# MotorAlarm2B.net
KiCad netlist of a schematic drawn in EAGLE
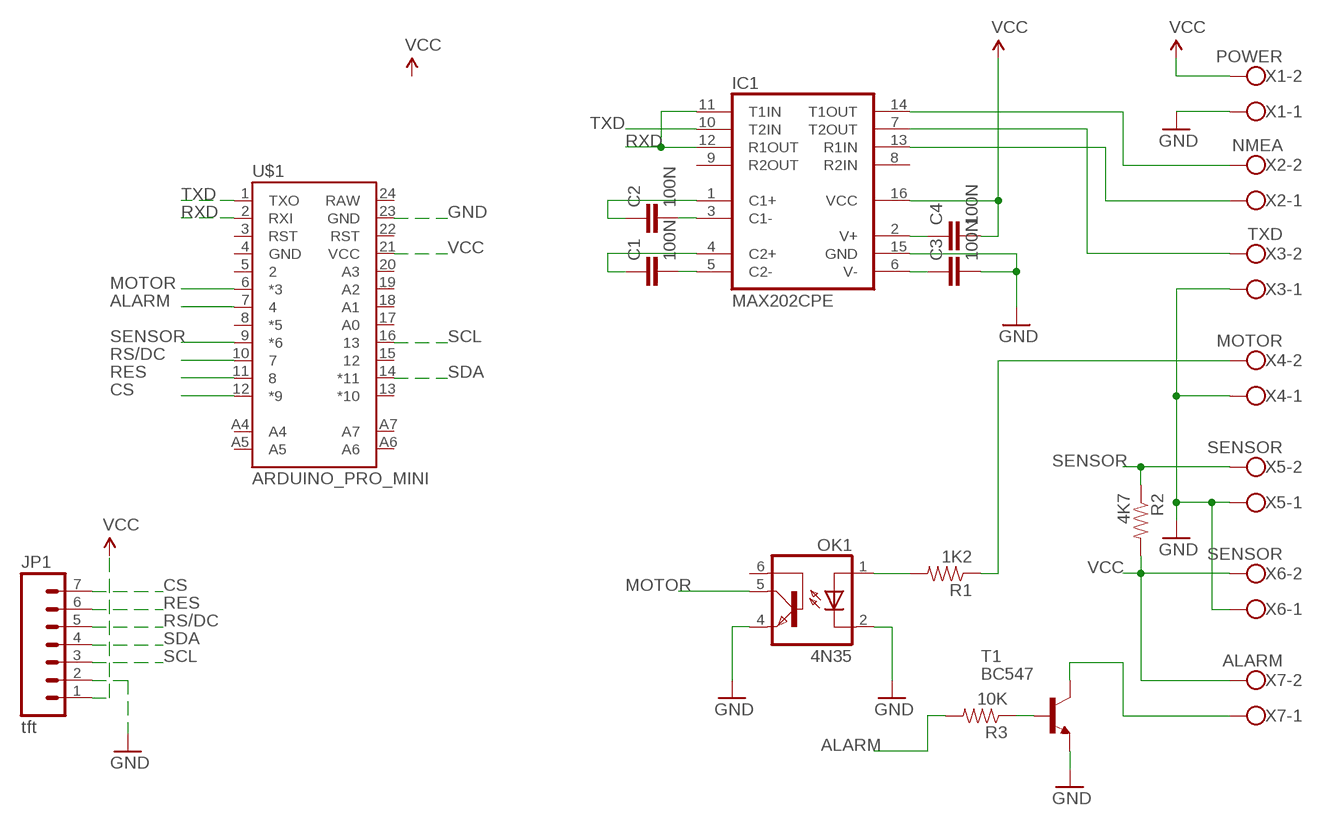
[diagram p0: schematic, sheet 1]

(export (version "E")
  (design (tool "Eeschema 10.0.6"))
  (components
    (comp (ref "C1")
      (value "100N")
      (footprint "eagle-import:CAP-PTH-SMALL")
      (libsource (lib "eagle-import") (part "CAPPTH"))
    )
    (comp (ref "C2")
      (value "100N")
      (footprint "eagle-import:CAP-PTH-SMALL")
      (libsource (lib "eagle-import") (part "CAPPTH"))
    )
    (comp (ref "C3")
      (value "100N")
      (footprint "eagle-import:CAP-PTH-SMALL")
      (libsource (lib "eagle-import") (part "CAPPTH"))
    )
    (comp (ref "C4")
      (value "100N")
      (footprint "eagle-import:CAP-PTH-SMALL")
      (libsource (lib "eagle-import") (part "CAPPTH"))
    )
    (comp (ref "IC1")
      (value "MAX202CPE")
      (footprint "eagle-import:DIL16")
      (fields (field (name "MF") "MAXIM") (field (name "MPN") "MAX202CPE+"))
      (libsource (lib "eagle-import") (part "MAX202CPE"))
    )
    (comp (ref "JP1")
      (value "tft")
      (footprint "eagle-import:1X07")
      (libsource (lib "eagle-import") (part "M07"))
    )
    (comp (ref "OK1")
      (value "4N35")
      (footprint "eagle-import:DIL06")
      (fields (field (name "MF") "FAIRCHILD SEMICONDUCTOR"))
      (libsource (lib "eagle-import") (part "4N35"))
    )
    (comp (ref "R1")
      (value "1K2")
      (footprint "eagle-import:AXIAL-0.4")
      (libsource (lib "eagle-import") (part "RESISTORPTH-1/4W"))
    )
    (comp (ref "R2")
      (value "4K7")
      (footprint "eagle-import:AXIAL-0.4")
      (libsource (lib "eagle-import") (part "RESISTORPTH-1/4W"))
    )
    (comp (ref "R3")
      (value "10K")
      (footprint "eagle-import:AXIAL-0.4")
      (libsource (lib "eagle-import") (part "RESISTORPTH-1/4W"))
    )
    (comp (ref "T1")
      (value "BC547")
      (footprint "eagle-import:TO92")
      (libsource (lib "eagle-import") (part "BC547"))
    )
    (comp (ref "U$1")
      (value "ARDUINO_PRO_MINI")
      (footprint "eagle-import:ARDUINO_PRO_MINI")
      (libsource (lib "eagle-import") (part "ARDUINO_PRO_MINI"))
    )
    (comp (ref "X1")
      (value "POWER")
      (footprint "eagle-import:W237-102")
      (fields (field (name "MPN") "237-102"))
      (libsource (lib "eagle-import") (part "W237-102"))
    )
    (comp (ref "X2")
      (value "NMEA")
      (footprint "eagle-import:W237-102")
      (fields (field (name "MPN") "237-102"))
      (libsource (lib "eagle-import") (part "W237-102"))
    )
    (comp (ref "X3")
      (value "TXD")
      (footprint "eagle-import:W237-102")
      (fields (field (name "MPN") "237-102"))
      (libsource (lib "eagle-import") (part "W237-102"))
    )
    (comp (ref "X4")
      (value "MOTOR")
      (footprint "eagle-import:W237-102")
      (fields (field (name "MPN") "237-102"))
      (libsource (lib "eagle-import") (part "W237-102"))
    )
    (comp (ref "X5")
      (value "SENSOR")
      (footprint "eagle-import:W237-102")
      (fields (field (name "MPN") "237-102"))
      (libsource (lib "eagle-import") (part "W237-102"))
    )
    (comp (ref "X6")
      (value "SENSOR")
      (footprint "eagle-import:W237-102")
      (fields (field (name "MPN") "237-102"))
      (libsource (lib "eagle-import") (part "W237-102"))
    )
    (comp (ref "X7")
      (value "ALARM")
      (footprint "eagle-import:W237-102")
      (fields (field (name "MPN") "237-102"))
      (libsource (lib "eagle-import") (part "W237-102"))
    )
  )
  (nets
    (net (code "1") (name "/ALARM") (class "Default")
      (node (ref "R3") (pin "P$2") (pinfunction "2_P$2") (pintype "passive"))
      (node (ref "U$1") (pin "7") (pinfunction "4_7") (pintype "bidirectional"))
    )
    (net (code "2") (name "/CS") (class "Default")
      (node (ref "JP1") (pin "7") (pinfunction "7_7") (pintype "passive"))
      (node (ref "U$1") (pin "12") (pinfunction "*9_12") (pintype "bidirectional"))
    )
    (net (code "3") (name "/MOTOR") (class "Default")
      (node (ref "OK1") (pin "5") (pinfunction "COL_5") (pintype "passive"))
      (node (ref "U$1") (pin "6") (pinfunction "*3_6") (pintype "bidirectional"))
    )
    (net (code "4") (name "/RES") (class "Default")
      (node (ref "JP1") (pin "6") (pinfunction "6_6") (pintype "passive"))
      (node (ref "U$1") (pin "11") (pinfunction "8_11") (pintype "bidirectional"))
    )
    (net (code "5") (name "/RS{slash}DC") (class "Default")
      (node (ref "JP1") (pin "5") (pinfunction "5_5") (pintype "passive"))
      (node (ref "U$1") (pin "10") (pinfunction "7_10") (pintype "bidirectional"))
    )
    (net (code "6") (name "/RXD") (class "Default")
      (node (ref "IC1") (pin "11") (pinfunction "T1IN_11") (pintype "input"))
      (node (ref "IC1") (pin "12") (pinfunction "R1OUT_12") (pintype "output"))
      (node (ref "U$1") (pin "2") (pinfunction "RXI_2") (pintype "bidirectional"))
    )
    (net (code "7") (name "/SCL") (class "Default")
      (node (ref "JP1") (pin "3") (pinfunction "3_3") (pintype "passive"))
      (node (ref "U$1") (pin "16") (pinfunction "13_16") (pintype "bidirectional"))
    )
    (net (code "8") (name "/SDA") (class "Default")
      (node (ref "JP1") (pin "4") (pinfunction "4_4") (pintype "passive"))
      (node (ref "U$1") (pin "14") (pinfunction "*11_14") (pintype "bidirectional"))
    )
    (net (code "9") (name "/SENSOR") (class "Default")
      (node (ref "R2") (pin "P$1") (pinfunction "1_P$1") (pintype "passive"))
      (node (ref "U$1") (pin "9") (pinfunction "*6_9") (pintype "bidirectional"))
      (node (ref "X5") (pin "2") (pinfunction "KL_2") (pintype "passive"))
    )
    (net (code "10") (name "/TXD") (class "Default")
      (node (ref "IC1") (pin "10") (pinfunction "T2IN_10") (pintype "input"))
      (node (ref "U$1") (pin "1") (pinfunction "TXO_1") (pintype "bidirectional"))
    )
    (net (code "11") (name "GND") (class "Default")
      (node (ref "C3") (pin "2") (pinfunction "2_2") (pintype "passive"))
      (node (ref "IC1") (pin "15") (pinfunction "GND_15") (pintype "power_in"))
      (node (ref "JP1") (pin "2") (pinfunction "2_2") (pintype "passive"))
      (node (ref "OK1") (pin "2") (pinfunction "C_2") (pintype "passive"))
      (node (ref "OK1") (pin "4") (pinfunction "EMI_4") (pintype "passive"))
      (node (ref "T1") (pin "1") (pinfunction "E_1") (pintype "passive"))
      (node (ref "U$1") (pin "23") (pinfunction "GND_23") (pintype "bidirectional"))
      (node (ref "X1") (pin "1") (pinfunction "KL_1") (pintype "passive"))
      (node (ref "X3") (pin "1") (pinfunction "KL_1") (pintype "passive"))
      (node (ref "X4") (pin "1") (pinfunction "KL_1") (pintype "passive"))
      (node (ref "X5") (pin "1") (pinfunction "KL_1") (pintype "passive"))
      (node (ref "X6") (pin "1") (pinfunction "KL_1") (pintype "passive"))
    )
    (net (code "12") (name "Net-(IC1-C1+)") (class "Default")
      (node (ref "C2") (pin "1") (pinfunction "1_1") (pintype "passive"))
      (node (ref "IC1") (pin "1") (pinfunction "C1+_1") (pintype "passive"))
    )
    (net (code "13") (name "Net-(IC1-C1-)") (class "Default")
      (node (ref "C2") (pin "2") (pinfunction "2_2") (pintype "passive"))
      (node (ref "IC1") (pin "3") (pinfunction "C1-_3") (pintype "passive"))
    )
    (net (code "14") (name "Net-(IC1-C2+)") (class "Default")
      (node (ref "C1") (pin "1") (pinfunction "1_1") (pintype "passive"))
      (node (ref "IC1") (pin "4") (pinfunction "C2+_4") (pintype "passive"))
    )
    (net (code "15") (name "Net-(IC1-C2-)") (class "Default")
      (node (ref "C1") (pin "2") (pinfunction "2_2") (pintype "passive"))
      (node (ref "IC1") (pin "5") (pinfunction "C2-_5") (pintype "passive"))
    )
    (net (code "16") (name "Net-(IC1-R1IN)") (class "Default")
      (node (ref "IC1") (pin "13") (pinfunction "R1IN_13") (pintype "input"))
      (node (ref "X2") (pin "1") (pinfunction "KL_1") (pintype "passive"))
    )
    (net (code "17") (name "Net-(IC1-T1OUT)") (class "Default")
      (node (ref "IC1") (pin "14") (pinfunction "T1OUT_14") (pintype "output"))
      (node (ref "X2") (pin "2") (pinfunction "KL_2") (pintype "passive"))
    )
    (net (code "18") (name "Net-(IC1-T2OUT)") (class "Default")
      (node (ref "IC1") (pin "7") (pinfunction "T2OUT_7") (pintype "output"))
      (node (ref "X3") (pin "2") (pinfunction "KL_2") (pintype "passive"))
    )
    (net (code "19") (name "Net-(IC1-V+)") (class "Default")
      (node (ref "C4") (pin "1") (pinfunction "1_1") (pintype "passive"))
      (node (ref "IC1") (pin "2") (pinfunction "V+_2") (pintype "power_in"))
    )
    (net (code "20") (name "Net-(IC1-V-)") (class "Default")
      (node (ref "C3") (pin "1") (pinfunction "1_1") (pintype "passive"))
      (node (ref "IC1") (pin "6") (pinfunction "V-_6") (pintype "power_in"))
    )
    (net (code "21") (name "Net-(OK1-A)") (class "Default")
      (node (ref "OK1") (pin "1") (pinfunction "A_1") (pintype "passive"))
      (node (ref "R1") (pin "P$2") (pinfunction "2_P$2") (pintype "passive"))
    )
    (net (code "22") (name "Net-(R1-1)") (class "Default")
      (node (ref "R1") (pin "P$1") (pinfunction "1_P$1") (pintype "passive"))
      (node (ref "X4") (pin "2") (pinfunction "KL_2") (pintype "passive"))
    )
    (net (code "23") (name "Net-(R3-1)") (class "Default")
      (node (ref "R3") (pin "P$1") (pinfunction "1_P$1") (pintype "passive"))
      (node (ref "T1") (pin "2") (pinfunction "B_2") (pintype "passive"))
    )
    (net (code "24") (name "Net-(T1-C)") (class "Default")
      (node (ref "T1") (pin "3") (pinfunction "C_3") (pintype "passive"))
      (node (ref "X7") (pin "1") (pinfunction "KL_1") (pintype "passive"))
    )
    (net (code "25") (name "VCC") (class "Default")
      (node (ref "C4") (pin "2") (pinfunction "2_2") (pintype "passive"))
      (node (ref "IC1") (pin "16") (pinfunction "VCC_16") (pintype "power_in"))
      (node (ref "JP1") (pin "1") (pinfunction "1_1") (pintype "passive"))
      (node (ref "R2") (pin "P$2") (pinfunction "2_P$2") (pintype "passive"))
      (node (ref "U$1") (pin "21") (pinfunction "VCC_21") (pintype "bidirectional"))
      (node (ref "X1") (pin "2") (pinfunction "KL_2") (pintype "passive"))
      (node (ref "X6") (pin "2") (pinfunction "KL_2") (pintype "passive"))
      (node (ref "X7") (pin "2") (pinfunction "KL_2") (pintype "passive"))
    )
    (net (code "26") (name "unconnected-(IC1-R2IN-Pad8)") (class "Default")
      (node (ref "IC1") (pin "8") (pinfunction "R2IN_8") (pintype "input"))
    )
    (net (code "27") (name "unconnected-(IC1-R2OUT-Pad9)") (class "Default")
      (node (ref "IC1") (pin "9") (pinfunction "R2OUT_9") (pintype "output"))
    )
    (net (code "28") (name "unconnected-(OK1-BAS-Pad6)") (class "Default")
      (node (ref "OK1") (pin "6") (pinfunction "BAS_6") (pintype "passive"))
    )
    (net (code "29") (name "unconnected-(U$1-*5-Pad8)") (class "Default")
      (node (ref "U$1") (pin "8") (pinfunction "*5_8") (pintype "bidirectional"))
    )
    (net (code "30") (name "unconnected-(U$1-*10-Pad13)") (class "Default")
      (node (ref "U$1") (pin "13") (pinfunction "*10_13") (pintype "bidirectional"))
    )
    (net (code "31") (name "unconnected-(U$1-2-Pad5)") (class "Default")
      (node (ref "U$1") (pin "5") (pinfunction "2_5") (pintype "bidirectional"))
    )
    (net (code "32") (name "unconnected-(U$1-12-Pad15)") (class "Default")
      (node (ref "U$1") (pin "15") (pinfunction "12_15") (pintype "bidirectional"))
    )
    (net (code "33") (name "unconnected-(U$1-A0-Pad17)") (class "Default")
      (node (ref "U$1") (pin "17") (pinfunction "A0_17") (pintype "bidirectional"))
    )
    (net (code "34") (name "unconnected-(U$1-A1-Pad18)") (class "Default")
      (node (ref "U$1") (pin "18") (pinfunction "A1_18") (pintype "bidirectional"))
    )
    (net (code "35") (name "unconnected-(U$1-A2-Pad19)") (class "Default")
      (node (ref "U$1") (pin "19") (pinfunction "A2_19") (pintype "bidirectional"))
    )
    (net (code "36") (name "unconnected-(U$1-A3-Pad20)") (class "Default")
      (node (ref "U$1") (pin "20") (pinfunction "A3_20") (pintype "bidirectional"))
    )
    (net (code "37") (name "unconnected-(U$1-GND-Pad4)") (class "Default")
      (node (ref "U$1") (pin "4") (pinfunction "GND_4") (pintype "bidirectional"))
    )
    (net (code "38") (name "unconnected-(U$1-PadA4)") (class "Default")
      (node (ref "U$1") (pin "A4") (pinfunction "A4_A4") (pintype "bidirectional"))
    )
    (net (code "39") (name "unconnected-(U$1-PadA5)") (class "Default")
      (node (ref "U$1") (pin "A5") (pinfunction "A5_A5") (pintype "bidirectional"))
    )
    (net (code "40") (name "unconnected-(U$1-PadA6)") (class "Default")
      (node (ref "U$1") (pin "A6") (pinfunction "A6_A6") (pintype "bidirectional"))
    )
    (net (code "41") (name "unconnected-(U$1-PadA7)") (class "Default")
      (node (ref "U$1") (pin "A7") (pinfunction "A7_A7") (pintype "bidirectional"))
    )
    (net (code "42") (name "unconnected-(U$1-RAW-Pad24)") (class "Default")
      (node (ref "U$1") (pin "24") (pinfunction "RAW_24") (pintype "bidirectional"))
    )
    (net (code "43") (name "unconnected-(U$1-RST-Pad3)") (class "Default")
      (node (ref "U$1") (pin "3") (pinfunction "RST_3") (pintype "bidirectional"))
    )
    (net (code "44") (name "unconnected-(U$1-RST-Pad22)") (class "Default")
      (node (ref "U$1") (pin "22") (pinfunction "RST_22") (pintype "bidirectional"))
    )
  )
)
